# RS232-Board.net
KiCad netlist of a schematic drawn in EAGLE
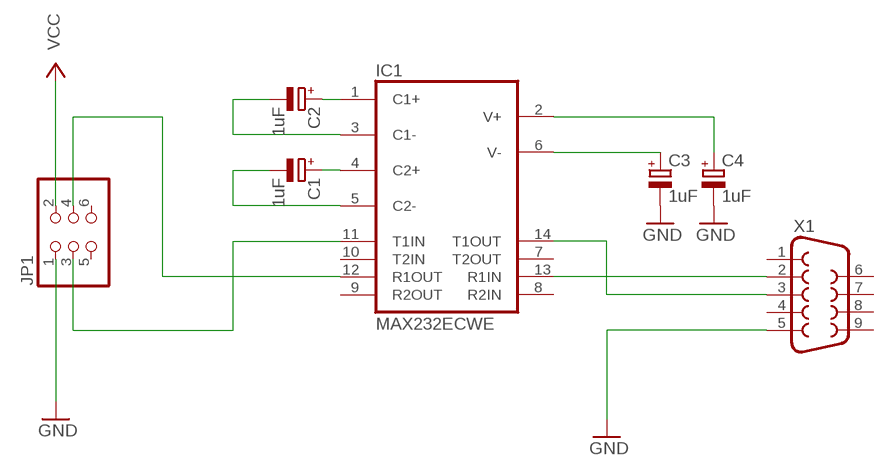
[diagram p0: schematic, sheet 1]

(export (version "E")
  (design (tool "Eeschema 10.0.6"))
  (components
    (comp (ref "C1")
      (value "1uF")
      (footprint "eagle-import:E2,5-6E")
      (libsource (lib "eagle-import") (part "CPOL-EUE2,5-6E"))
    )
    (comp (ref "C2")
      (value "1uF")
      (footprint "eagle-import:E2,5-6E")
      (libsource (lib "eagle-import") (part "CPOL-EUE2,5-6E"))
    )
    (comp (ref "C3")
      (value "1uF")
      (footprint "eagle-import:E2,5-6E")
      (libsource (lib "eagle-import") (part "CPOL-EUE2,5-6E"))
    )
    (comp (ref "C4")
      (value "1uF")
      (footprint "eagle-import:E2,5-6E")
      (libsource (lib "eagle-import") (part "CPOL-EUE2,5-6E"))
    )
    (comp (ref "IC1")
      (value "MAX232ECWE")
      (footprint "eagle-import:SO16L")
      (fields (field (name "MF") "MAXIM") (field (name "MPN") "MAX232ECWE+"))
      (libsource (lib "eagle-import") (part "MAX232ECWE"))
    )
    (comp (ref "JP1")
      (value "PINHD-2X3")
      (footprint "eagle-import:2X03")
      (libsource (lib "eagle-import") (part "PINHD-2X3"))
    )
    (comp (ref "X1")
      (value "F09H")
      (footprint "eagle-import:F09H")
      (libsource (lib "eagle-import") (part "F09H"))
    )
  )
  (nets
    (net (code "1") (name "GND") (class "Default")
      (node (ref "C3") (pin "-") (pinfunction "-_-") (pintype "passive"))
      (node (ref "C4") (pin "-") (pinfunction "-_-") (pintype "passive"))
      (node (ref "JP1") (pin "1") (pinfunction "1_1") (pintype "passive"))
      (node (ref "X1") (pin "5") (pinfunction "5_5") (pintype "passive"))
    )
    (net (code "2") (name "Net-(IC1A-C1+)") (class "Default")
      (node (ref "C2") (pin "+") (pinfunction "+_+") (pintype "passive"))
      (node (ref "IC1") (pin "1") (pinfunction "C1+_1") (pintype "bidirectional"))
    )
    (net (code "3") (name "Net-(IC1A-C1-)") (class "Default")
      (node (ref "C2") (pin "-") (pinfunction "-_-") (pintype "passive"))
      (node (ref "IC1") (pin "3") (pinfunction "C1-_3") (pintype "bidirectional"))
    )
    (net (code "4") (name "Net-(IC1A-C2+)") (class "Default")
      (node (ref "C1") (pin "+") (pinfunction "+_+") (pintype "passive"))
      (node (ref "IC1") (pin "4") (pinfunction "C2+_4") (pintype "bidirectional"))
    )
    (net (code "5") (name "Net-(IC1A-C2-)") (class "Default")
      (node (ref "C1") (pin "-") (pinfunction "-_-") (pintype "passive"))
      (node (ref "IC1") (pin "5") (pinfunction "C2-_5") (pintype "bidirectional"))
    )
    (net (code "6") (name "Net-(IC1A-R1IN)") (class "Default")
      (node (ref "IC1") (pin "13") (pinfunction "R1IN_13") (pintype "input"))
      (node (ref "X1") (pin "2") (pinfunction "2_2") (pintype "passive"))
    )
    (net (code "7") (name "Net-(IC1A-R1OUT)") (class "Default")
      (node (ref "IC1") (pin "12") (pinfunction "R1OUT_12") (pintype "output"))
      (node (ref "JP1") (pin "4") (pinfunction "4_4") (pintype "passive"))
    )
    (net (code "8") (name "Net-(IC1A-T1IN)") (class "Default")
      (node (ref "IC1") (pin "11") (pinfunction "T1IN_11") (pintype "input"))
      (node (ref "JP1") (pin "3") (pinfunction "3_3") (pintype "passive"))
    )
    (net (code "9") (name "Net-(IC1A-T1OUT)") (class "Default")
      (node (ref "IC1") (pin "14") (pinfunction "T1OUT_14") (pintype "output"))
      (node (ref "X1") (pin "3") (pinfunction "3_3") (pintype "passive"))
    )
    (net (code "10") (name "Net-(IC1A-V+)") (class "Default")
      (node (ref "C4") (pin "+") (pinfunction "+_+") (pintype "passive"))
      (node (ref "IC1") (pin "2") (pinfunction "V+_2") (pintype "bidirectional"))
    )
    (net (code "11") (name "Net-(IC1A-V-)") (class "Default")
      (node (ref "C3") (pin "+") (pinfunction "+_+") (pintype "passive"))
      (node (ref "IC1") (pin "6") (pinfunction "V-_6") (pintype "bidirectional"))
    )
    (net (code "12") (name "VCC") (class "Default")
      (node (ref "JP1") (pin "2") (pinfunction "2_2") (pintype "passive"))
    )
    (net (code "13") (name "unconnected-(IC1A-R2IN-Pad8)") (class "Default")
      (node (ref "IC1") (pin "8") (pinfunction "R2IN_8") (pintype "input"))
    )
    (net (code "14") (name "unconnected-(IC1A-R2OUT-Pad9)") (class "Default")
      (node (ref "IC1") (pin "9") (pinfunction "R2OUT_9") (pintype "output"))
    )
    (net (code "15") (name "unconnected-(IC1A-T2IN-Pad10)") (class "Default")
      (node (ref "IC1") (pin "10") (pinfunction "T2IN_10") (pintype "input"))
    )
    (net (code "16") (name "unconnected-(IC1A-T2OUT-Pad7)") (class "Default")
      (node (ref "IC1") (pin "7") (pinfunction "T2OUT_7") (pintype "output"))
    )
    (net (code "17") (name "unconnected-(JP1-Pad5)") (class "Default")
      (node (ref "JP1") (pin "5") (pinfunction "5_5") (pintype "passive"))
    )
    (net (code "18") (name "unconnected-(JP1-Pad6)") (class "Default")
      (node (ref "JP1") (pin "6") (pinfunction "6_6") (pintype "passive"))
    )
    (net (code "19") (name "unconnected-(X1-Pad1)") (class "Default")
      (node (ref "X1") (pin "1") (pinfunction "1_1") (pintype "passive"))
    )
    (net (code "20") (name "unconnected-(X1-Pad4)") (class "Default")
      (node (ref "X1") (pin "4") (pinfunction "4_4") (pintype "passive"))
    )
    (net (code "21") (name "unconnected-(X1-Pad6)") (class "Default")
      (node (ref "X1") (pin "6") (pinfunction "6_6") (pintype "passive"))
    )
    (net (code "22") (name "unconnected-(X1-Pad7)") (class "Default")
      (node (ref "X1") (pin "7") (pinfunction "7_7") (pintype "passive"))
    )
    (net (code "23") (name "unconnected-(X1-Pad8)") (class "Default")
      (node (ref "X1") (pin "8") (pinfunction "8_8") (pintype "passive"))
    )
    (net (code "24") (name "unconnected-(X1-Pad9)") (class "Default")
      (node (ref "X1") (pin "9") (pinfunction "9_9") (pintype "passive"))
    )
  )
)
